# quadcopter.net
KiCad netlist of a schematic drawn in EAGLE
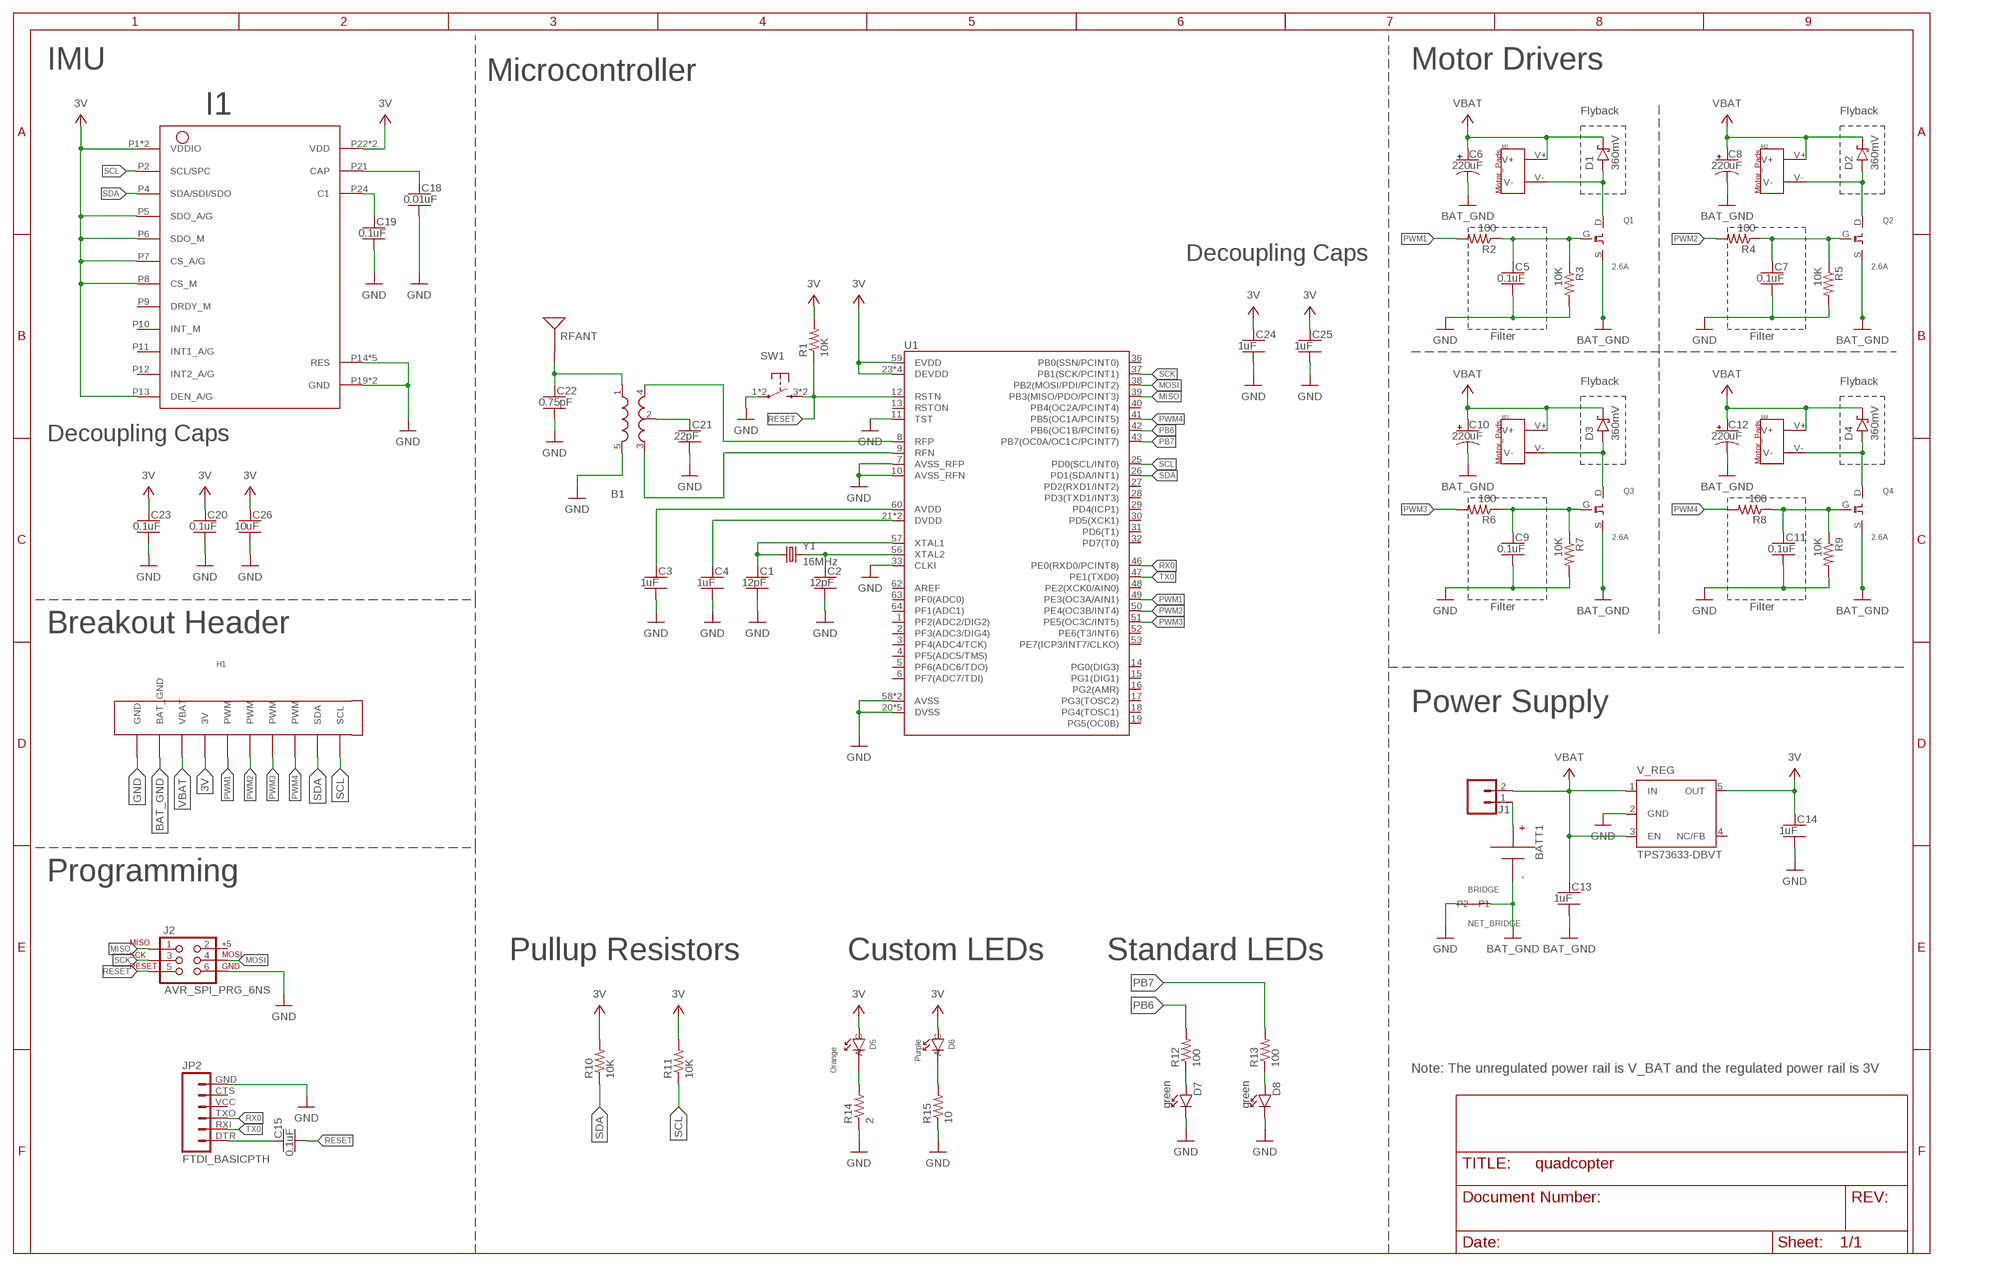
[diagram p0: schematic, sheet 1]

(export (version "E")
  (design (tool "Eeschema 10.0.6"))
  (components
    (comp (ref "B1")
      (value "BALUN0805")
      (footprint "eagle-import:BALUN")
      (fields
        (field (name "MFR") "Wurth Electronics Inc")
        (field (name "MPN") "748421245")
        (field (name "CREATOR") "Swanson")
        (field (name "REVIEWER") "Swanson")
      )
      (libsource (lib "eagle-import") (part "BALUN0805"))
    )
    (comp (ref "BATT1")
      (value "BATTERY-HUBSAN-W/HOLDER")
      (footprint "eagle-import:BATTERY-W_HOLDER-380MAH-HUBSAN")
      (fields
        (field (name "MFR") "HUBSAN")
        (field (name "MPN") "X4-H107C-8-in-1")
        (field (name "CREATOR") "Swanson")
        (field (name "REVIEWER") "Swanson")
      )
      (libsource (lib "eagle-import") (part "BATTERY-HUBSAN-W/HOLDER"))
    )
    (comp (ref "BRIDGE")
      (value "NET_BRIDGE")
      (footprint "eagle-import:NET_BRIDGE")
      (fields (field (name "CREATOR") "AGONZALES"))
      (libsource (lib "eagle-import") (part "NET_BRIDGE"))
    )
    (comp (ref "C1")
      (value "12pF")
      (footprint "eagle-import:CAPC2012X140_HS")
      (fields
        (field (name "MFR") "Murata Electronics North America")
        (field (name "MPN") "GRM21A5C2E120JW01D")
        (field (name "CREATOR") "Swanson")
        (field (name "REVIEWER") "Swanson")
      )
      (libsource (lib "eagle-import") (part "CAPACITOR-NP_SMD-2012-0805_CERAMIC-12PF"))
    )
    (comp (ref "C2")
      (value "12pF")
      (footprint "eagle-import:CAPC2012X140_HS")
      (fields
        (field (name "MFR") "Murata Electronics North America")
        (field (name "MPN") "GRM21A5C2E120JW01D")
        (field (name "CREATOR") "Swanson")
        (field (name "REVIEWER") "Swanson")
      )
      (libsource (lib "eagle-import") (part "CAPACITOR-NP_SMD-2012-0805_CERAMIC-12PF"))
    )
    (comp (ref "C3")
      (value "1uF")
      (footprint "eagle-import:CAPC2012X140_HS")
      (fields
        (field (name "MFR") "Taiyo Yuden")
        (field (name "MPN") "TMK212B7105KG-T")
        (field (name "CREATOR") "Swanson")
        (field (name "REVIEWER") "Swanson")
      )
      (libsource (lib "eagle-import") (part "CAPACITOR-NP_SMD-2012-0805_CERAMIC-1UF"))
    )
    (comp (ref "C4")
      (value "1uF")
      (footprint "eagle-import:CAPC2012X140_HS")
      (fields
        (field (name "MFR") "Taiyo Yuden")
        (field (name "MPN") "TMK212B7105KG-T")
        (field (name "CREATOR") "Swanson")
        (field (name "REVIEWER") "Swanson")
      )
      (libsource (lib "eagle-import") (part "CAPACITOR-NP_SMD-2012-0805_CERAMIC-1UF"))
    )
    (comp (ref "C5")
      (value "0.1uF")
      (footprint "eagle-import:CAPC2012X140_HS")
      (fields
        (field (name "MFR") "TDK")
        (field (name "MPN") "C2012X7R2A104K125AA")
        (field (name "CREATOR") "Swanson")
        (field (name "REVIEWER") "Swanson")
      )
      (libsource (lib "eagle-import") (part "CAPACITOR-NP_SMD-2012-0805_CERAMIC-0.1UF"))
    )
    (comp (ref "C6")
      (value "220uF")
      (footprint "eagle-import:CAPMP7343X310_HS")
      (fields
        (field (name "MFR") "AVX Corporation")
        (field (name "MPN") "TAJD227K006RNJ")
        (field (name "CREATOR") "Swanson")
        (field (name "REVIEWER") "Swanson")
      )
      (libsource (lib "eagle-import") (part "CAPACITOR-POL_SMD-7043-D_TANTALUM-220UF"))
    )
    (comp (ref "C7")
      (value "0.1uF")
      (footprint "eagle-import:CAPC2012X140_HS")
      (fields
        (field (name "MFR") "TDK")
        (field (name "MPN") "C2012X7R2A104K125AA")
        (field (name "CREATOR") "Swanson")
        (field (name "REVIEWER") "Swanson")
      )
      (libsource (lib "eagle-import") (part "CAPACITOR-NP_SMD-2012-0805_CERAMIC-0.1UF"))
    )
    (comp (ref "C8")
      (value "220uF")
      (footprint "eagle-import:CAPMP7343X310_HS")
      (fields
        (field (name "MFR") "AVX Corporation")
        (field (name "MPN") "TAJD227K006RNJ")
        (field (name "CREATOR") "Swanson")
        (field (name "REVIEWER") "Swanson")
      )
      (libsource (lib "eagle-import") (part "CAPACITOR-POL_SMD-7043-D_TANTALUM-220UF"))
    )
    (comp (ref "C9")
      (value "0.1uF")
      (footprint "eagle-import:CAPC2012X140_HS")
      (fields
        (field (name "MFR") "TDK")
        (field (name "MPN") "C2012X7R2A104K125AA")
        (field (name "CREATOR") "Swanson")
        (field (name "REVIEWER") "Swanson")
      )
      (libsource (lib "eagle-import") (part "CAPACITOR-NP_SMD-2012-0805_CERAMIC-0.1UF"))
    )
    (comp (ref "C10")
      (value "220uF")
      (footprint "eagle-import:CAPMP7343X310_HS")
      (fields
        (field (name "MFR") "AVX Corporation")
        (field (name "MPN") "TAJD227K006RNJ")
        (field (name "CREATOR") "Swanson")
        (field (name "REVIEWER") "Swanson")
      )
      (libsource (lib "eagle-import") (part "CAPACITOR-POL_SMD-7043-D_TANTALUM-220UF"))
    )
    (comp (ref "C11")
      (value "0.1uF")
      (footprint "eagle-import:CAPC2012X140_HS")
      (fields
        (field (name "MFR") "TDK")
        (field (name "MPN") "C2012X7R2A104K125AA")
        (field (name "CREATOR") "Swanson")
        (field (name "REVIEWER") "Swanson")
      )
      (libsource (lib "eagle-import") (part "CAPACITOR-NP_SMD-2012-0805_CERAMIC-0.1UF"))
    )
    (comp (ref "C12")
      (value "220uF")
      (footprint "eagle-import:CAPMP7343X310_HS")
      (fields
        (field (name "MFR") "AVX Corporation")
        (field (name "MPN") "TAJD227K006RNJ")
        (field (name "CREATOR") "Swanson")
        (field (name "REVIEWER") "Swanson")
      )
      (libsource (lib "eagle-import") (part "CAPACITOR-POL_SMD-7043-D_TANTALUM-220UF"))
    )
    (comp (ref "C13")
      (value "1uF")
      (footprint "eagle-import:CAPC2012X140_HS")
      (fields
        (field (name "MFR") "Taiyo Yuden")
        (field (name "MPN") "TMK212B7105KG-T")
        (field (name "CREATOR") "Swanson")
        (field (name "REVIEWER") "Swanson")
      )
      (libsource (lib "eagle-import") (part "CAPACITOR-NP_SMD-2012-0805_CERAMIC-1UF"))
    )
    (comp (ref "C14")
      (value "1uF")
      (footprint "eagle-import:CAPC2012X140_HS")
      (fields
        (field (name "MFR") "Taiyo Yuden")
        (field (name "MPN") "TMK212B7105KG-T")
        (field (name "CREATOR") "Swanson")
        (field (name "REVIEWER") "Swanson")
      )
      (libsource (lib "eagle-import") (part "CAPACITOR-NP_SMD-2012-0805_CERAMIC-1UF"))
    )
    (comp (ref "C15")
      (value "0.1uF")
      (footprint "eagle-import:CAPC2012X140_HS")
      (fields
        (field (name "MFR") "TDK")
        (field (name "MPN") "C2012X7R2A104K125AA")
        (field (name "CREATOR") "Swanson")
        (field (name "REVIEWER") "Swanson")
      )
      (libsource (lib "eagle-import") (part "CAPACITOR-NP_SMD-2012-0805_CERAMIC-0.1UF"))
    )
    (comp (ref "C18")
      (value "0.01uF")
      (footprint "eagle-import:CAPC2012X140_HS")
      (fields
        (field (name "MFR") "Knowles Syfer")
        (field (name "MPN") "0805J0500104KJT")
        (field (name "CREATOR") "Swanson")
        (field (name "REVIEWER") "Swanson")
      )
      (libsource (lib "eagle-import") (part "CAPACITOR-NP_SMD-2012-0805_CERAMIC-0.01UF"))
    )
    (comp (ref "C19")
      (value "0.1uF")
      (footprint "eagle-import:CAPC2012X140_HS")
      (fields
        (field (name "MFR") "TDK")
        (field (name "MPN") "C2012X7R2A104K125AA")
        (field (name "CREATOR") "Swanson")
        (field (name "REVIEWER") "Swanson")
      )
      (libsource (lib "eagle-import") (part "CAPACITOR-NP_SMD-2012-0805_CERAMIC-0.1UF"))
    )
    (comp (ref "C20")
      (value "0.1uF")
      (footprint "eagle-import:CAPC2012X140_HS")
      (fields
        (field (name "MFR") "TDK")
        (field (name "MPN") "C2012X7R2A104K125AA")
        (field (name "CREATOR") "Swanson")
        (field (name "REVIEWER") "Swanson")
      )
      (libsource (lib "eagle-import") (part "CAPACITOR-NP_SMD-2012-0805_CERAMIC-0.1UF"))
    )
    (comp (ref "C21")
      (value "22pF")
      (footprint "eagle-import:CAPC2012X140_HS")
      (fields
        (field (name "MFR") "Murata Electronics North America")
        (field (name "MPN") "GRM21A5C2E220JW01D")
        (field (name "CREATOR") "Swanson")
        (field (name "REVIEWER") "Swanson")
      )
      (libsource (lib "eagle-import") (part "CAPACITOR-NP_SMD-2012-0805_CERAMIC-22PF"))
    )
    (comp (ref "C22")
      (value "0.75pF")
      (footprint "eagle-import:CAPC2012X140_HS")
      (fields
        (field (name "MFR") "Murata Electronics North America")
        (field (name "MPN") "GQM2195C2AR75CB01D")
        (field (name "CREATOR") "Swanson")
        (field (name "REVIEWER") "Swanson")
      )
      (libsource (lib "eagle-import") (part "CAPACITOR-NP_SMD-2012-0805_CERAMIC-0.75PF"))
    )
    (comp (ref "C23")
      (value "0.1uF")
      (footprint "eagle-import:CAPC2012X140_HS")
      (fields
        (field (name "MFR") "TDK")
        (field (name "MPN") "C2012X7R2A104K125AA")
        (field (name "CREATOR") "Swanson")
        (field (name "REVIEWER") "Swanson")
      )
      (libsource (lib "eagle-import") (part "CAPACITOR-NP_SMD-2012-0805_CERAMIC-0.1UF"))
    )
    (comp (ref "C24")
      (value "1uF")
      (footprint "eagle-import:CAPC2012X140_HS")
      (fields
        (field (name "MFR") "Taiyo Yuden")
        (field (name "MPN") "TMK212B7105KG-T")
        (field (name "CREATOR") "Swanson")
        (field (name "REVIEWER") "Swanson")
      )
      (libsource (lib "eagle-import") (part "CAPACITOR-NP_SMD-2012-0805_CERAMIC-1UF"))
    )
    (comp (ref "C25")
      (value "1uF")
      (footprint "eagle-import:CAPC2012X140_HS")
      (fields
        (field (name "MFR") "Taiyo Yuden")
        (field (name "MPN") "TMK212B7105KG-T")
        (field (name "CREATOR") "Swanson")
        (field (name "REVIEWER") "Swanson")
      )
      (libsource (lib "eagle-import") (part "CAPACITOR-NP_SMD-2012-0805_CERAMIC-1UF"))
    )
    (comp (ref "C26")
      (value "10uF")
      (footprint "eagle-import:CAPC2012X140_HS")
      (fields
        (field (name "MFR") "TDK Corporation")
        (field (name "MPN") "C2012X5R1E106M085AC")
        (field (name "CREATOR") "Swanson")
        (field (name "REVIEWER") "Swanson")
      )
      (libsource (lib "eagle-import") (part "CAPACITOR-NP_SMD-2012-0805_CERAMIC-10UF"))
    )
    (comp (ref "D1")
      (value "360mV")
      (footprint "eagle-import:SOD3716X135_HS")
      (fields
        (field (name "MFR") "Toshiba Semiconductor and Storage")
        (field (name "MPN") "CRS08(TE85L,Q,M)")
        (field (name "CREATOR") "Swanson")
        (field (name "REVIEWER") "Swanson")
      )
      (libsource (lib "eagle-import") (part "DIODE-SCHOTTKY_SMD-SOD123-360MV"))
    )
    (comp (ref "D2")
      (value "360mV")
      (footprint "eagle-import:SOD3716X135_HS")
      (fields
        (field (name "MFR") "Toshiba Semiconductor and Storage")
        (field (name "MPN") "CRS08(TE85L,Q,M)")
        (field (name "CREATOR") "Swanson")
        (field (name "REVIEWER") "Swanson")
      )
      (libsource (lib "eagle-import") (part "DIODE-SCHOTTKY_SMD-SOD123-360MV"))
    )
    (comp (ref "D3")
      (value "360mV")
      (footprint "eagle-import:SOD3716X135_HS")
      (fields
        (field (name "MFR") "Toshiba Semiconductor and Storage")
        (field (name "MPN") "CRS08(TE85L,Q,M)")
        (field (name "CREATOR") "Swanson")
        (field (name "REVIEWER") "Swanson")
      )
      (libsource (lib "eagle-import") (part "DIODE-SCHOTTKY_SMD-SOD123-360MV"))
    )
    (comp (ref "D4")
      (value "360mV")
      (footprint "eagle-import:SOD3716X135_HS")
      (fields
        (field (name "MFR") "Toshiba Semiconductor and Storage")
        (field (name "MPN") "CRS08(TE85L,Q,M)")
        (field (name "CREATOR") "Swanson")
        (field (name "REVIEWER") "Swanson")
      )
      (libsource (lib "eagle-import") (part "DIODE-SCHOTTKY_SMD-SOD123-360MV"))
    )
    (comp (ref "D5")
      (value "Orange")
      (footprint "eagle-import:LED_ORANGE")
      (fields
        (field (name "MFR") "Lumileds")
        (field (name "MPN") "L135-O615003500001")
        (field (name "CREATOR") "Ben Phan")
      )
      (libsource (lib "eagle-import") (part "LED_ORANGE"))
    )
    (comp (ref "D6")
      (value "Purple")
      (footprint "eagle-import:LED_PURPLE")
      (fields
        (field (name "MFR") "Lumileds")
        (field (name "MPN") "L1SP-PRP2003500000")
        (field (name "CREATOR") "Ben Phan")
      )
      (libsource (lib "eagle-import") (part "LED_PURPLE"))
    )
    (comp (ref "D7")
      (value "green")
      (footprint "eagle-import:LEDSC125X200X120-2_HS")
      (fields
        (field (name "MFR") "Lite-On Inc")
        (field (name "MPN") "LTST-C170GKT")
        (field (name "CREATOR") "Swanson")
        (field (name "REVIEWER") "Swanson")
      )
      (libsource (lib "eagle-import") (part "DIODE-LED_SMD-2012-0805-GREEN"))
    )
    (comp (ref "D8")
      (value "green")
      (footprint "eagle-import:LEDSC125X200X120-2_HS")
      (fields
        (field (name "MFR") "Lite-On Inc")
        (field (name "MPN") "LTST-C170GKT")
        (field (name "CREATOR") "Swanson")
        (field (name "REVIEWER") "Swanson")
      )
      (libsource (lib "eagle-import") (part "DIODE-LED_SMD-2012-0805-GREEN"))
    )
    (comp (ref "H1")
      (value "BREAKOUT_HEADER")
      (footprint "eagle-import:BREAKOUT_HEADER")
      (fields (field (name "CREATOR") "Ben Phan"))
      (libsource (lib "eagle-import") (part "BREAKOUT_HEADER"))
    )
    (comp (ref "I1")
      (value "IMU_LSM9DS1TR")
      (footprint "eagle-import:IMU_LSM9DS1TR")
      (fields (field (name "MFR") "STMicroelectronics") (field (name "CREATOR") "AGONZALES"))
      (libsource (lib "eagle-import") (part "IMU_LSM9DS1TR"))
    )
    (comp (ref "J1")
      (value "MALE_HEADER_2POS-2X1-0.1IN")
      (footprint "eagle-import:MALE_HEADER_2X1_0.1IN")
      (fields
        (field (name "MFR") "3M")
        (field (name "MPN") "961102-6404-AR")
        (field (name "CREATOR") "SWANSON")
        (field (name "REVIEWER") "Swanson")
      )
      (libsource (lib "eagle-import") (part "MALE_HEADER_2POS-2X1-0.1IN"))
    )
    (comp (ref "J2")
      (value "AVR_SPI_PRG_6NS")
      (footprint "eagle-import:2X3-NS")
      (fields
        (field (name "MFR") "Amphenol FCI")
        (field (name "MPN") "67997-206HLF")
        (field (name "CREATOR") "Swanson")
        (field (name "REVIEWER") "Swanson")
      )
      (libsource (lib "eagle-import") (part "AVR_SPI_PRG_6NS"))
    )
    (comp (ref "JP2")
      (value "FTDI_BASICPTH")
      (footprint "eagle-import:FTDI_BASIC")
      (fields
        (field (name "MFR") "Amphenol FCI")
        (field (name "MPN") "68016-406HLF")
        (field (name "CREATOR") "Swanson")
        (field (name "REVIEWER") "Swanson")
      )
      (libsource (lib "eagle-import") (part "FTDI_BASICPTH"))
    )
    (comp (ref "M1")
      (value "MOTOR_PADS")
      (footprint "eagle-import:MOTOR_PADS")
      (fields
        (field (name "MFR") "NA")
        (field (name "CREATOR") "Swanson")
        (field (name "REVIEWER") "Swanson")
      )
      (libsource (lib "eagle-import") (part "MOTOR_PADS"))
    )
    (comp (ref "M2")
      (value "MOTOR_PADS")
      (footprint "eagle-import:MOTOR_PADS")
      (fields
        (field (name "MFR") "NA")
        (field (name "CREATOR") "Swanson")
        (field (name "REVIEWER") "Swanson")
      )
      (libsource (lib "eagle-import") (part "MOTOR_PADS"))
    )
    (comp (ref "M3")
      (value "MOTOR_PADS")
      (footprint "eagle-import:MOTOR_PADS")
      (fields
        (field (name "MFR") "NA")
        (field (name "CREATOR") "Swanson")
        (field (name "REVIEWER") "Swanson")
      )
      (libsource (lib "eagle-import") (part "MOTOR_PADS"))
    )
    (comp (ref "M4")
      (value "MOTOR_PADS")
      (footprint "eagle-import:MOTOR_PADS")
      (fields
        (field (name "MFR") "NA")
        (field (name "CREATOR") "Swanson")
        (field (name "REVIEWER") "Swanson")
      )
      (libsource (lib "eagle-import") (part "MOTOR_PADS"))
    )
    (comp (ref "Q1")
      (value "2.6A")
      (footprint "eagle-import:MOSFET_N-CHANNEL")
      (fields
        (field (name "MFR") "Vishay Siliconix")
        (field (name "MPN") "SI2302CDS-T1-E3")
        (field (name "CREATOR") "Ben Phan")
      )
      (libsource (lib "eagle-import") (part "N_CHANNEL_FET"))
    )
    (comp (ref "Q2")
      (value "2.6A")
      (footprint "eagle-import:MOSFET_N-CHANNEL")
      (fields
        (field (name "MFR") "Vishay Siliconix")
        (field (name "MPN") "SI2302CDS-T1-E3")
        (field (name "CREATOR") "Ben Phan")
      )
      (libsource (lib "eagle-import") (part "N_CHANNEL_FET"))
    )
    (comp (ref "Q3")
      (value "2.6A")
      (footprint "eagle-import:MOSFET_N-CHANNEL")
      (fields
        (field (name "MFR") "Vishay Siliconix")
        (field (name "MPN") "SI2302CDS-T1-E3")
        (field (name "CREATOR") "Ben Phan")
      )
      (libsource (lib "eagle-import") (part "N_CHANNEL_FET"))
    )
    (comp (ref "Q4")
      (value "2.6A")
      (footprint "eagle-import:MOSFET_N-CHANNEL")
      (fields
        (field (name "MFR") "Vishay Siliconix")
        (field (name "MPN") "SI2302CDS-T1-E3")
        (field (name "CREATOR") "Ben Phan")
      )
      (libsource (lib "eagle-import") (part "N_CHANNEL_FET"))
    )
    (comp (ref "R1")
      (value "10K")
      (footprint "eagle-import:RESC2012X60_HS")
      (fields
        (field (name "MFR") "Yageo")
        (field (name "MPN") "RC0805JR-0710KL")
        (field (name "CREATOR") "Swanson")
        (field (name "REVIEWER") "Swanson")
      )
      (libsource (lib "eagle-import") (part "RESISTOR_SMD-2012-0805-10K"))
    )
    (comp (ref "R2")
      (value "100")
      (footprint "eagle-import:RESC2012X60_HS")
      (fields
        (field (name "MFR") "Yageo")
        (field (name "MPN") "RC0805JR-07100RL")
        (field (name "CREATOR") "Swanson")
        (field (name "REVIEWER") "Swanson")
      )
      (libsource (lib "eagle-import") (part "RESISTOR_SMD-2012-0805-100"))
    )
    (comp (ref "R3")
      (value "10K")
      (footprint "eagle-import:RESC2012X60_HS")
      (fields
        (field (name "MFR") "Yageo")
        (field (name "MPN") "RC0805JR-0710KL")
        (field (name "CREATOR") "Swanson")
        (field (name "REVIEWER") "Swanson")
      )
      (libsource (lib "eagle-import") (part "RESISTOR_SMD-2012-0805-10K"))
    )
    (comp (ref "R4")
      (value "100")
      (footprint "eagle-import:RESC2012X60_HS")
      (fields
        (field (name "MFR") "Yageo")
        (field (name "MPN") "RC0805JR-07100RL")
        (field (name "CREATOR") "Swanson")
        (field (name "REVIEWER") "Swanson")
      )
      (libsource (lib "eagle-import") (part "RESISTOR_SMD-2012-0805-100"))
    )
    (comp (ref "R5")
      (value "10K")
      (footprint "eagle-import:RESC2012X60_HS")
      (fields
        (field (name "MFR") "Yageo")
        (field (name "MPN") "RC0805JR-0710KL")
        (field (name "CREATOR") "Swanson")
        (field (name "REVIEWER") "Swanson")
      )
      (libsource (lib "eagle-import") (part "RESISTOR_SMD-2012-0805-10K"))
    )
    (comp (ref "R6")
      (value "100")
      (footprint "eagle-import:RESC2012X60_HS")
      (fields
        (field (name "MFR") "Yageo")
        (field (name "MPN") "RC0805JR-07100RL")
        (field (name "CREATOR") "Swanson")
        (field (name "REVIEWER") "Swanson")
      )
      (libsource (lib "eagle-import") (part "RESISTOR_SMD-2012-0805-100"))
    )
    (comp (ref "R7")
      (value "10K")
      (footprint "eagle-import:RESC2012X60_HS")
      (fields
        (field (name "MFR") "Yageo")
        (field (name "MPN") "RC0805JR-0710KL")
        (field (name "CREATOR") "Swanson")
        (field (name "REVIEWER") "Swanson")
      )
      (libsource (lib "eagle-import") (part "RESISTOR_SMD-2012-0805-10K"))
    )
    (comp (ref "R8")
      (value "100")
      (footprint "eagle-import:RESC2012X60_HS")
      (fields
        (field (name "MFR") "Yageo")
        (field (name "MPN") "RC0805JR-07100RL")
        (field (name "CREATOR") "Swanson")
        (field (name "REVIEWER") "Swanson")
      )
      (libsource (lib "eagle-import") (part "RESISTOR_SMD-2012-0805-100"))
    )
    (comp (ref "R9")
      (value "10K")
      (footprint "eagle-import:RESC2012X60_HS")
      (fields
        (field (name "MFR") "Yageo")
        (field (name "MPN") "RC0805JR-0710KL")
        (field (name "CREATOR") "Swanson")
        (field (name "REVIEWER") "Swanson")
      )
      (libsource (lib "eagle-import") (part "RESISTOR_SMD-2012-0805-10K"))
    )
    (comp (ref "R10")
      (value "10K")
      (footprint "eagle-import:RESC2012X60_HS")
      (fields
        (field (name "MFR") "Yageo")
        (field (name "MPN") "RC0805JR-0710KL")
        (field (name "CREATOR") "Swanson")
        (field (name "REVIEWER") "Swanson")
      )
      (libsource (lib "eagle-import") (part "RESISTOR_SMD-2012-0805-10K"))
    )
    (comp (ref "R11")
      (value "10K")
      (footprint "eagle-import:RESC2012X60_HS")
      (fields
        (field (name "MFR") "Yageo")
        (field (name "MPN") "RC0805JR-0710KL")
        (field (name "CREATOR") "Swanson")
        (field (name "REVIEWER") "Swanson")
      )
      (libsource (lib "eagle-import") (part "RESISTOR_SMD-2012-0805-10K"))
    )
    (comp (ref "R12")
      (value "100")
      (footprint "eagle-import:RESC2012X60_HS")
      (fields
        (field (name "MFR") "Yageo")
        (field (name "MPN") "RC0805JR-07100RL")
        (field (name "CREATOR") "Swanson")
        (field (name "REVIEWER") "Swanson")
      )
      (libsource (lib "eagle-import") (part "RESISTOR_SMD-2012-0805-100"))
    )
    (comp (ref "R13")
      (value "100")
      (footprint "eagle-import:RESC2012X60_HS")
      (fields
        (field (name "MFR") "Yageo")
        (field (name "MPN") "RC0805JR-07100RL")
        (field (name "CREATOR") "Swanson")
        (field (name "REVIEWER") "Swanson")
      )
      (libsource (lib "eagle-import") (part "RESISTOR_SMD-2012-0805-100"))
    )
    (comp (ref "R14")
      (value "2")
      (footprint "eagle-import:RESISTOR_0805")
      (fields (field (name "CREATOR") "AGONZALES"))
      (libsource (lib "eagle-import") (part "0805_RES2_OHM"))
    )
    (comp (ref "R15")
      (value "10")
      (footprint "eagle-import:RESISTOR_0805")
      (fields (field (name "CREATOR") "AGONZALES"))
      (libsource (lib "eagle-import") (part "0805_RES10_OHM"))
    )
    (comp (ref "RFANT")
      (value "ANTENNA2SMD5")
      (footprint "eagle-import:ANTENNA-CHIP5")
      (fields
        (field (name "MFR") "Linx Technologies Inc.")
        (field (name "MPN") "ANT-2.45-CHP-T")
        (field (name "CREATOR") "Swanson")
        (field (name "REVIEWER") "Swanson")
      )
      (libsource (lib "eagle-import") (part "ANTENNA2SMD5"))
    )
    (comp (ref "SW1")
      (value "PUSHBUTTON_SMD-VERTICAL-1")
      (footprint "eagle-import:TE_FSM8JSMA_HS")
      (fields
        (field (name "MFR") "TE Connectivity Alcoswitch Switches")
        (field (name "MPN") "FSM4JSMA")
        (field (name "CREATOR") "Swanson")
        (field (name "REVIEWER") "Swanson")
      )
      (libsource (lib "eagle-import") (part "PUSHBUTTON_SMD-VERTICAL-1"))
    )
    (comp (ref "U1")
      (value "ATMEGA128RFA1")
      (footprint "eagle-import:QFN-64")
      (fields
        (field (name "MFR") "Atmel")
        (field (name "MPN") "ATMEGA128RFA1-ZUR00")
        (field (name "CREATOR") "Swanson")
        (field (name "REVIEWER") "Swanson")
      )
      (libsource (lib "eagle-import") (part "ATMEGA128RFA1"))
    )
    (comp (ref "V_REG")
      (value "TPS73633-DBVT")
      (footprint "eagle-import:SOT23-DBV")
      (fields
        (field (name "MFR") "Texas Instruments")
        (field (name "MPN") "LP3985IM5X-3.0/NOPB")
        (field (name "CREATOR") "Swanson")
        (field (name "REVIEWER") "Swanson")
      )
      (libsource (lib "eagle-import") (part "TPS73633-DBVT"))
    )
    (comp (ref "Y1")
      (value "16MHz")
      (footprint "eagle-import:CRYSTAL-SMD-5X3")
      (fields
        (field (name "MFR") "Abracon LLC")
        (field (name "MPN") "ABM3B-16.000MHZ-B2-T")
        (field (name "CREATOR") "Swanson")
        (field (name "REVIEWER") "Swanson")
      )
      (libsource (lib "eagle-import") (part "CRYSTAL5X3"))
    )
  )
  (nets
    (net (code "1") (name "3V") (class "Default")
      (node (ref "C14") (pin "1") (pinfunction "1_1") (pintype "passive"))
      (node (ref "C20") (pin "1") (pinfunction "1_1") (pintype "passive"))
      (node (ref "C23") (pin "1") (pinfunction "1_1") (pintype "passive"))
      (node (ref "C24") (pin "1") (pinfunction "1_1") (pintype "passive"))
      (node (ref "C25") (pin "1") (pinfunction "1_1") (pintype "passive"))
      (node (ref "C26") (pin "1") (pinfunction "1_1") (pintype "passive"))
      (node (ref "D5") (pin "A") (pinfunction "A_A") (pintype "bidirectional"))
      (node (ref "D6") (pin "A") (pinfunction "A_A") (pintype "bidirectional"))
      (node (ref "H1") (pin "1") (pinfunction "3V_1") (pintype "bidirectional"))
      (node (ref "I1") (pin "P1") (pinfunction "VDDIO_P1") (pintype "bidirectional"))
      (node (ref "I1") (pin "P13") (pinfunction "DEN_A/G_P13") (pintype "bidirectional"))
      (node (ref "I1") (pin "P22") (pinfunction "VDD_P22") (pintype "bidirectional"))
      (node (ref "I1") (pin "P23") (pinfunction "VDD_P23") (pintype "bidirectional"))
      (node (ref "I1") (pin "P3") (pinfunction "VDDIO_P3") (pintype "bidirectional"))
      (node (ref "I1") (pin "P5") (pinfunction "SDO_A/G_P5") (pintype "bidirectional"))
      (node (ref "I1") (pin "P6") (pinfunction "SDO_M_P6") (pintype "bidirectional"))
      (node (ref "I1") (pin "P7") (pinfunction "CS_A/G_P7") (pintype "bidirectional"))
      (node (ref "I1") (pin "P8") (pinfunction "CS_M_P8") (pintype "bidirectional"))
      (node (ref "R1") (pin "2") (pinfunction "2_2") (pintype "passive"))
      (node (ref "R10") (pin "2") (pinfunction "2_2") (pintype "passive"))
      (node (ref "R11") (pin "2") (pinfunction "2_2") (pintype "passive"))
      (node (ref "U1") (pin "23") (pinfunction "DEVDD_23") (pintype "bidirectional"))
      (node (ref "U1") (pin "34") (pinfunction "DEVDD_34") (pintype "bidirectional"))
      (node (ref "U1") (pin "44") (pinfunction "DEVDD_44") (pintype "bidirectional"))
      (node (ref "U1") (pin "54") (pinfunction "DEVDD_54") (pintype "bidirectional"))
      (node (ref "U1") (pin "59") (pinfunction "EVDD_59") (pintype "bidirectional"))
      (node (ref "V_REG") (pin "5") (pinfunction "OUT_5") (pintype "passive"))
    )
    (net (code "2") (name "BAT_GND") (class "Default")
      (node (ref "BATT1") (pin "-") (pinfunction "N_-") (pintype "bidirectional"))
      (node (ref "BRIDGE") (pin "P2") (pinfunction "P2_P2") (pintype "bidirectional"))
      (node (ref "C10") (pin "2") (pinfunction "-_2") (pintype "passive"))
      (node (ref "C12") (pin "2") (pinfunction "-_2") (pintype "passive"))
      (node (ref "C13") (pin "2") (pinfunction "2_2") (pintype "passive"))
      (node (ref "C6") (pin "2") (pinfunction "-_2") (pintype "passive"))
      (node (ref "C8") (pin "2") (pinfunction "-_2") (pintype "passive"))
      (node (ref "H1") (pin "2") (pinfunction "BAT_GND_2") (pintype "bidirectional"))
      (node (ref "Q1") (pin "S") (pinfunction "S_S") (pintype "bidirectional"))
      (node (ref "Q2") (pin "S") (pinfunction "S_S") (pintype "bidirectional"))
      (node (ref "Q3") (pin "S") (pinfunction "S_S") (pintype "bidirectional"))
      (node (ref "Q4") (pin "S") (pinfunction "S_S") (pintype "bidirectional"))
    )
    (net (code "3") (name "GND") (class "Default")
      (node (ref "B1") (pin "5") (pinfunction "GND_5") (pintype "bidirectional"))
      (node (ref "BRIDGE") (pin "P1") (pinfunction "P1_P1") (pintype "bidirectional"))
      (node (ref "C1") (pin "2") (pinfunction "2_2") (pintype "passive"))
      (node (ref "C11") (pin "2") (pinfunction "2_2") (pintype "passive"))
      (node (ref "C14") (pin "2") (pinfunction "2_2") (pintype "passive"))
      (node (ref "C18") (pin "2") (pinfunction "2_2") (pintype "passive"))
      (node (ref "C19") (pin "2") (pinfunction "2_2") (pintype "passive"))
      (node (ref "C2") (pin "2") (pinfunction "2_2") (pintype "passive"))
      (node (ref "C20") (pin "2") (pinfunction "2_2") (pintype "passive"))
      (node (ref "C21") (pin "2") (pinfunction "2_2") (pintype "passive"))
      (node (ref "C22") (pin "2") (pinfunction "2_2") (pintype "passive"))
      (node (ref "C23") (pin "2") (pinfunction "2_2") (pintype "passive"))
      (node (ref "C24") (pin "2") (pinfunction "2_2") (pintype "passive"))
      (node (ref "C25") (pin "2") (pinfunction "2_2") (pintype "passive"))
      (node (ref "C26") (pin "2") (pinfunction "2_2") (pintype "passive"))
      (node (ref "C3") (pin "2") (pinfunction "2_2") (pintype "passive"))
      (node (ref "C4") (pin "2") (pinfunction "2_2") (pintype "passive"))
      (node (ref "C5") (pin "2") (pinfunction "2_2") (pintype "passive"))
      (node (ref "C7") (pin "2") (pinfunction "2_2") (pintype "passive"))
      (node (ref "C9") (pin "2") (pinfunction "2_2") (pintype "passive"))
      (node (ref "D7") (pin "C") (pinfunction "C_C") (pintype "passive"))
      (node (ref "D8") (pin "C") (pinfunction "C_C") (pintype "passive"))
      (node (ref "H1") (pin "3") (pinfunction "GND_3") (pintype "bidirectional"))
      (node (ref "I1") (pin "P14") (pinfunction "RES_P14") (pintype "bidirectional"))
      (node (ref "I1") (pin "P15") (pinfunction "RES_P15") (pintype "bidirectional"))
      (node (ref "I1") (pin "P16") (pinfunction "RES_P16") (pintype "bidirectional"))
      (node (ref "I1") (pin "P17") (pinfunction "RES_P17") (pintype "bidirectional"))
      (node (ref "I1") (pin "P18") (pinfunction "RES_P18") (pintype "bidirectional"))
      (node (ref "I1") (pin "P19") (pinfunction "GND_P19") (pintype "bidirectional"))
      (node (ref "I1") (pin "P20") (pinfunction "GND_P20") (pintype "bidirectional"))
      (node (ref "J2") (pin "6") (pinfunction "6_6") (pintype "passive"))
      (node (ref "JP2") (pin "GND") (pinfunction "6_GND") (pintype "passive"))
      (node (ref "R14") (pin "IN") (pinfunction "1_IN") (pintype "passive"))
      (node (ref "R15") (pin "IN") (pinfunction "1_IN") (pintype "passive"))
      (node (ref "R3") (pin "2") (pinfunction "2_2") (pintype "passive"))
      (node (ref "R5") (pin "2") (pinfunction "2_2") (pintype "passive"))
      (node (ref "R7") (pin "2") (pinfunction "2_2") (pintype "passive"))
      (node (ref "R9") (pin "2") (pinfunction "2_2") (pintype "passive"))
      (node (ref "SW1") (pin "1") (pinfunction "1_1") (pintype "passive"))
      (node (ref "SW1") (pin "2") (pinfunction "1_2") (pintype "passive"))
      (node (ref "U1") (pin "10") (pinfunction "AVSS_RFN_10") (pintype "bidirectional"))
      (node (ref "U1") (pin "11") (pinfunction "TST_11") (pintype "bidirectional"))
      (node (ref "U1") (pin "20") (pinfunction "DVSS_20") (pintype "bidirectional"))
      (node (ref "U1") (pin "24") (pinfunction "DVSS_24") (pintype "bidirectional"))
      (node (ref "U1") (pin "33") (pinfunction "CLKI_33") (pintype "bidirectional"))
      (node (ref "U1") (pin "35") (pinfunction "DVSS_35") (pintype "bidirectional"))
      (node (ref "U1") (pin "45") (pinfunction "DVSS_45") (pintype "bidirectional"))
      (node (ref "U1") (pin "55") (pinfunction "DVSS_55") (pintype "bidirectional"))
      (node (ref "U1") (pin "58") (pinfunction "AVSS_58") (pintype "bidirectional"))
      (node (ref "U1") (pin "61") (pinfunction "AVSS_61") (pintype "bidirectional"))
      (node (ref "U1") (pin "7") (pinfunction "AVSS_RFP_7") (pintype "bidirectional"))
      (node (ref "V_REG") (pin "2") (pinfunction "GND_2") (pintype "input"))
    )
    (net (code "4") (name "MISO") (class "Default")
      (node (ref "J2") (pin "1") (pinfunction "1_1") (pintype "passive"))
      (node (ref "U1") (pin "39") (pinfunction "PB3(MISO/PDO/PCINT3)_39") (pintype "bidirectional"))
    )
    (net (code "5") (name "MOSI") (class "Default")
      (node (ref "J2") (pin "4") (pinfunction "4_4") (pintype "passive"))
      (node (ref "U1") (pin "38") (pinfunction "PB2(MOSI/PDI/PCINT2)_38") (pintype "bidirectional"))
    )
    (net (code "6") (name "Net-(B1-GND-Pad2)") (class "Default")
      (node (ref "B1") (pin "2") (pinfunction "GND_2") (pintype "bidirectional"))
      (node (ref "C21") (pin "1") (pinfunction "1_1") (pintype "passive"))
    )
    (net (code "7") (name "Net-(B1-IN)") (class "Default")
      (node (ref "B1") (pin "1") (pinfunction "IN_1") (pintype "bidirectional"))
      (node (ref "C22") (pin "1") (pinfunction "1_1") (pintype "passive"))
      (node (ref "RFANT") (pin "FEED") (pinfunction "SIGNAL_FEED") (pintype "bidirectional"))
    )
    (net (code "8") (name "Net-(B1-OUT1)") (class "Default")
      (node (ref "B1") (pin "4") (pinfunction "OUT1_4") (pintype "bidirectional"))
      (node (ref "U1") (pin "8") (pinfunction "RFP_8") (pintype "bidirectional"))
    )
    (net (code "9") (name "Net-(B1-OUT2)") (class "Default")
      (node (ref "B1") (pin "3") (pinfunction "OUT2_3") (pintype "bidirectional"))
      (node (ref "U1") (pin "9") (pinfunction "RFN_9") (pintype "bidirectional"))
    )
    (net (code "10") (name "Net-(BATT1-P)") (class "Default")
      (node (ref "BATT1") (pin "+") (pinfunction "P_+") (pintype "bidirectional"))
      (node (ref "J1") (pin "1") (pinfunction "1_1") (pintype "passive"))
    )
    (net (code "11") (name "Net-(C4-Pad1)") (class "Default")
      (node (ref "C4") (pin "1") (pinfunction "1_1") (pintype "passive"))
      (node (ref "U1") (pin "21") (pinfunction "DVDD_21") (pintype "bidirectional"))
      (node (ref "U1") (pin "22") (pinfunction "DVDD_22") (pintype "bidirectional"))
    )
    (net (code "12") (name "Net-(C5-Pad1)") (class "Default")
      (node (ref "C5") (pin "1") (pinfunction "1_1") (pintype "passive"))
      (node (ref "Q1") (pin "G") (pinfunction "G_G") (pintype "bidirectional"))
      (node (ref "R2") (pin "1") (pinfunction "1_1") (pintype "passive"))
      (node (ref "R3") (pin "1") (pinfunction "1_1") (pintype "passive"))
    )
    (net (code "13") (name "Net-(C7-Pad1)") (class "Default")
      (node (ref "C7") (pin "1") (pinfunction "1_1") (pintype "passive"))
      (node (ref "Q2") (pin "G") (pinfunction "G_G") (pintype "bidirectional"))
      (node (ref "R4") (pin "1") (pinfunction "1_1") (pintype "passive"))
      (node (ref "R5") (pin "1") (pinfunction "1_1") (pintype "passive"))
    )
    (net (code "14") (name "Net-(C9-Pad1)") (class "Default")
      (node (ref "C9") (pin "1") (pinfunction "1_1") (pintype "passive"))
      (node (ref "Q3") (pin "G") (pinfunction "G_G") (pintype "bidirectional"))
      (node (ref "R6") (pin "1") (pinfunction "1_1") (pintype "passive"))
      (node (ref "R7") (pin "1") (pinfunction "1_1") (pintype "passive"))
    )
    (net (code "15") (name "Net-(C11-Pad1)") (class "Default")
      (node (ref "C11") (pin "1") (pinfunction "1_1") (pintype "passive"))
      (node (ref "Q4") (pin "G") (pinfunction "G_G") (pintype "bidirectional"))
      (node (ref "R8") (pin "1") (pinfunction "1_1") (pintype "passive"))
      (node (ref "R9") (pin "1") (pinfunction "1_1") (pintype "passive"))
    )
    (net (code "16") (name "Net-(D1-PadA)") (class "Default")
      (node (ref "D1") (pin "A") (pinfunction "A_A") (pintype "passive"))
      (node (ref "M1") (pin "V-") (pinfunction "V-_V-") (pintype "bidirectional"))
      (node (ref "Q1") (pin "D") (pinfunction "D_D") (pintype "bidirectional"))
    )
    (net (code "17") (name "Net-(D2-PadA)") (class "Default")
      (node (ref "D2") (pin "A") (pinfunction "A_A") (pintype "passive"))
      (node (ref "M2") (pin "V-") (pinfunction "V-_V-") (pintype "bidirectional"))
      (node (ref "Q2") (pin "D") (pinfunction "D_D") (pintype "bidirectional"))
    )
    (net (code "18") (name "Net-(D3-PadA)") (class "Default")
      (node (ref "D3") (pin "A") (pinfunction "A_A") (pintype "passive"))
      (node (ref "M3") (pin "V-") (pinfunction "V-_V-") (pintype "bidirectional"))
      (node (ref "Q3") (pin "D") (pinfunction "D_D") (pintype "bidirectional"))
    )
    (net (code "19") (name "Net-(D4-PadA)") (class "Default")
      (node (ref "D4") (pin "A") (pinfunction "A_A") (pintype "passive"))
      (node (ref "M4") (pin "V-") (pinfunction "V-_V-") (pintype "bidirectional"))
      (node (ref "Q4") (pin "D") (pinfunction "D_D") (pintype "bidirectional"))
    )
    (net (code "20") (name "Net-(D7-PadA)") (class "Default")
      (node (ref "D7") (pin "A") (pinfunction "A_A") (pintype "passive"))
      (node (ref "R12") (pin "1") (pinfunction "1_1") (pintype "passive"))
    )
    (net (code "21") (name "Net-(D8-PadA)") (class "Default")
      (node (ref "D8") (pin "A") (pinfunction "A_A") (pintype "passive"))
      (node (ref "R13") (pin "1") (pinfunction "1_1") (pintype "passive"))
    )
    (net (code "22") (name "Net-(I1-C1)") (class "Default")
      (node (ref "C19") (pin "1") (pinfunction "1_1") (pintype "passive"))
      (node (ref "I1") (pin "P24") (pinfunction "C1_P24") (pintype "bidirectional"))
    )
    (net (code "23") (name "Net-(I1-CAP)") (class "Default")
      (node (ref "C18") (pin "1") (pinfunction "1_1") (pintype "passive"))
      (node (ref "I1") (pin "P21") (pinfunction "CAP_P21") (pintype "bidirectional"))
    )
    (net (code "24") (name "Net-(JP2-1)") (class "Default")
      (node (ref "C15") (pin "1") (pinfunction "1_1") (pintype "passive"))
      (node (ref "JP2") (pin "DTR") (pinfunction "1_DTR") (pintype "passive"))
    )
    (net (code "25") (name "Net-(R14-2)") (class "Default")
      (node (ref "D5") (pin "C") (pinfunction "C_C") (pintype "bidirectional"))
      (node (ref "R14") (pin "OUT") (pinfunction "2_OUT") (pintype "passive"))
    )
    (net (code "26") (name "Net-(R15-2)") (class "Default")
      (node (ref "D6") (pin "C") (pinfunction "C_C") (pintype "bidirectional"))
      (node (ref "R15") (pin "OUT") (pinfunction "2_OUT") (pintype "passive"))
    )
    (net (code "27") (name "Net-(U1-AVDD)") (class "Default")
      (node (ref "C3") (pin "1") (pinfunction "1_1") (pintype "passive"))
      (node (ref "U1") (pin "60") (pinfunction "AVDD_60") (pintype "bidirectional"))
    )
    (net (code "28") (name "Net-(U1-XTAL1)") (class "Default")
      (node (ref "C1") (pin "1") (pinfunction "1_1") (pintype "passive"))
      (node (ref "U1") (pin "57") (pinfunction "XTAL1_57") (pintype "bidirectional"))
      (node (ref "Y1") (pin "1") (pinfunction "1_1") (pintype "passive"))
    )
    (net (code "29") (name "Net-(U1-XTAL2)") (class "Default")
      (node (ref "C2") (pin "1") (pinfunction "1_1") (pintype "passive"))
      (node (ref "U1") (pin "56") (pinfunction "XTAL2_56") (pintype "bidirectional"))
      (node (ref "Y1") (pin "3") (pinfunction "2_3") (pintype "passive"))
    )
    (net (code "30") (name "PB6") (class "Default")
      (node (ref "R12") (pin "2") (pinfunction "2_2") (pintype "passive"))
      (node (ref "U1") (pin "42") (pinfunction "PB6(OC1B/PCINT6)_42") (pintype "bidirectional"))
    )
    (net (code "31") (name "PB7") (class "Default")
      (node (ref "R13") (pin "2") (pinfunction "2_2") (pintype "passive"))
      (node (ref "U1") (pin "43") (pinfunction "PB7(OC0A/OC1C/PCINT7)_43") (pintype "bidirectional"))
    )
    (net (code "32") (name "PWM1") (class "Default")
      (node (ref "H1") (pin "4") (pinfunction "PWM_4") (pintype "bidirectional"))
      (node (ref "R2") (pin "2") (pinfunction "2_2") (pintype "passive"))
      (node (ref "U1") (pin "49") (pinfunction "PE3(OC3A/AIN1)_49") (pintype "bidirectional"))
    )
    (net (code "33") (name "PWM2") (class "Default")
      (node (ref "H1") (pin "5") (pinfunction "PWM_5") (pintype "bidirectional"))
      (node (ref "R4") (pin "2") (pinfunction "2_2") (pintype "passive"))
      (node (ref "U1") (pin "50") (pinfunction "PE4(OC3B/INT4)_50") (pintype "bidirectional"))
    )
    (net (code "34") (name "PWM3") (class "Default")
      (node (ref "H1") (pin "6") (pinfunction "PWM_6") (pintype "bidirectional"))
      (node (ref "R6") (pin "2") (pinfunction "2_2") (pintype "passive"))
      (node (ref "U1") (pin "51") (pinfunction "PE5(OC3C/INT5)_51") (pintype "bidirectional"))
    )
    (net (code "35") (name "PWM4") (class "Default")
      (node (ref "H1") (pin "7") (pinfunction "PWM_7") (pintype "bidirectional"))
      (node (ref "R8") (pin "2") (pinfunction "2_2") (pintype "passive"))
      (node (ref "U1") (pin "41") (pinfunction "PB5(OC1A/PCINT5)_41") (pintype "bidirectional"))
    )
    (net (code "36") (name "RESET") (class "Default")
      (node (ref "C15") (pin "2") (pinfunction "2_2") (pintype "passive"))
      (node (ref "J2") (pin "5") (pinfunction "5_5") (pintype "passive"))
      (node (ref "R1") (pin "1") (pinfunction "1_1") (pintype "passive"))
      (node (ref "SW1") (pin "3") (pinfunction "2_3") (pintype "passive"))
      (node (ref "SW1") (pin "4") (pinfunction "2_4") (pintype "passive"))
      (node (ref "U1") (pin "12") (pinfunction "RSTN_12") (pintype "bidirectional"))
    )
    (net (code "37") (name "RX0") (class "Default")
      (node (ref "JP2") (pin "TXO") (pinfunction "3_TXO") (pintype "passive"))
      (node (ref "U1") (pin "46") (pinfunction "PE0(RXD0/PCINT8)_46") (pintype "bidirectional"))
    )
    (net (code "38") (name "SCK") (class "Default")
      (node (ref "J2") (pin "3") (pinfunction "3_3") (pintype "passive"))
      (node (ref "U1") (pin "37") (pinfunction "PB1(SCK/PCINT1)_37") (pintype "bidirectional"))
    )
    (net (code "39") (name "SCL") (class "Default")
      (node (ref "H1") (pin "8") (pinfunction "SCL_8") (pintype "bidirectional"))
      (node (ref "I1") (pin "P2") (pinfunction "SCL/SPC_P2") (pintype "bidirectional"))
      (node (ref "R11") (pin "1") (pinfunction "1_1") (pintype "passive"))
      (node (ref "U1") (pin "25") (pinfunction "PD0(SCL/INT0)_25") (pintype "bidirectional"))
    )
    (net (code "40") (name "SDA") (class "Default")
      (node (ref "H1") (pin "9") (pinfunction "SDA_9") (pintype "bidirectional"))
      (node (ref "I1") (pin "P4") (pinfunction "SDA/SDI/SDO_P4") (pintype "bidirectional"))
      (node (ref "R10") (pin "1") (pinfunction "1_1") (pintype "passive"))
      (node (ref "U1") (pin "26") (pinfunction "PD1(SDA/INT1)_26") (pintype "bidirectional"))
    )
    (net (code "41") (name "TX0") (class "Default")
      (node (ref "JP2") (pin "RXI") (pinfunction "2_RXI") (pintype "passive"))
      (node (ref "U1") (pin "47") (pinfunction "PE1(TXD0)_47") (pintype "bidirectional"))
    )
    (net (code "42") (name "VBAT") (class "Default")
      (node (ref "C10") (pin "1") (pinfunction "+_1") (pintype "passive"))
      (node (ref "C12") (pin "1") (pinfunction "+_1") (pintype "passive"))
      (node (ref "C13") (pin "1") (pinfunction "1_1") (pintype "passive"))
      (node (ref "C6") (pin "1") (pinfunction "+_1") (pintype "passive"))
      (node (ref "C8") (pin "1") (pinfunction "+_1") (pintype "passive"))
      (node (ref "D1") (pin "C") (pinfunction "C_C") (pintype "passive"))
      (node (ref "D2") (pin "C") (pinfunction "C_C") (pintype "passive"))
      (node (ref "D3") (pin "C") (pinfunction "C_C") (pintype "passive"))
      (node (ref "D4") (pin "C") (pinfunction "C_C") (pintype "passive"))
      (node (ref "H1") (pin "10") (pinfunction "VBAT_10") (pintype "bidirectional"))
      (node (ref "J1") (pin "2") (pinfunction "2_2") (pintype "passive"))
      (node (ref "M1") (pin "V+") (pinfunction "V+_V+") (pintype "bidirectional"))
      (node (ref "M2") (pin "V+") (pinfunction "V+_V+") (pintype "bidirectional"))
      (node (ref "M3") (pin "V+") (pinfunction "V+_V+") (pintype "bidirectional"))
      (node (ref "M4") (pin "V+") (pinfunction "V+_V+") (pintype "bidirectional"))
      (node (ref "V_REG") (pin "1") (pinfunction "IN_1") (pintype "input"))
      (node (ref "V_REG") (pin "3") (pinfunction "EN_3") (pintype "input"))
    )
    (net (code "43") (name "unconnected-(I1-DRDY_M-PadP9)") (class "Default")
      (node (ref "I1") (pin "P9") (pinfunction "DRDY_M_P9") (pintype "bidirectional"))
    )
    (net (code "44") (name "unconnected-(I1-INT1_A{slash}G-PadP11)") (class "Default")
      (node (ref "I1") (pin "P11") (pinfunction "INT1_A/G_P11") (pintype "bidirectional"))
    )
    (net (code "45") (name "unconnected-(I1-INT2_A{slash}G-PadP12)") (class "Default")
      (node (ref "I1") (pin "P12") (pinfunction "INT2_A/G_P12") (pintype "bidirectional"))
    )
    (net (code "46") (name "unconnected-(I1-INT_M-PadP10)") (class "Default")
      (node (ref "I1") (pin "P10") (pinfunction "INT_M_P10") (pintype "bidirectional"))
    )
    (net (code "47") (name "unconnected-(J2-Pad2)") (class "Default")
      (node (ref "J2") (pin "2") (pinfunction "2_2") (pintype "passive"))
    )
    (net (code "48") (name "unconnected-(JP2-4-PadVCC)") (class "Default")
      (node (ref "JP2") (pin "VCC") (pinfunction "4_VCC") (pintype "passive"))
    )
    (net (code "49") (name "unconnected-(JP2-5-PadCTS)") (class "Default")
      (node (ref "JP2") (pin "CTS") (pinfunction "5_CTS") (pintype "passive"))
    )
    (net (code "50") (name "unconnected-(U1-AREF-Pad62)") (class "Default")
      (node (ref "U1") (pin "62") (pinfunction "AREF_62") (pintype "bidirectional"))
    )
    (net (code "51") (name "unconnected-(U1-PB0(SSN{slash}PCINT0)-Pad36)") (class "Default")
      (node (ref "U1") (pin "36") (pinfunction "PB0(SSN/PCINT0)_36") (pintype "bidirectional"))
    )
    (net (code "52") (name "unconnected-(U1-PB4(OC2A{slash}PCINT4)-Pad40)") (class "Default")
      (node (ref "U1") (pin "40") (pinfunction "PB4(OC2A/PCINT4)_40") (pintype "bidirectional"))
    )
    (net (code "53") (name "unconnected-(U1-PD2(RXD1{slash}INT2)-Pad27)") (class "Default")
      (node (ref "U1") (pin "27") (pinfunction "PD2(RXD1/INT2)_27") (pintype "bidirectional"))
    )
    (net (code "54") (name "unconnected-(U1-PD3(TXD1{slash}INT3)-Pad28)") (class "Default")
      (node (ref "U1") (pin "28") (pinfunction "PD3(TXD1/INT3)_28") (pintype "bidirectional"))
    )
    (net (code "55") (name "unconnected-(U1-PD4(ICP1)-Pad29)") (class "Default")
      (node (ref "U1") (pin "29") (pinfunction "PD4(ICP1)_29") (pintype "bidirectional"))
    )
    (net (code "56") (name "unconnected-(U1-PD5(XCK1)-Pad30)") (class "Default")
      (node (ref "U1") (pin "30") (pinfunction "PD5(XCK1)_30") (pintype "bidirectional"))
    )
    (net (code "57") (name "unconnected-(U1-PD6(T1)-Pad31)") (class "Default")
      (node (ref "U1") (pin "31") (pinfunction "PD6(T1)_31") (pintype "bidirectional"))
    )
    (net (code "58") (name "unconnected-(U1-PD7(T0)-Pad32)") (class "Default")
      (node (ref "U1") (pin "32") (pinfunction "PD7(T0)_32") (pintype "bidirectional"))
    )
    (net (code "59") (name "unconnected-(U1-PE2(XCK0{slash}AIN0)-Pad48)") (class "Default")
      (node (ref "U1") (pin "48") (pinfunction "PE2(XCK0/AIN0)_48") (pintype "bidirectional"))
    )
    (net (code "60") (name "unconnected-(U1-PE6(T3{slash}INT6)-Pad52)") (class "Default")
      (node (ref "U1") (pin "52") (pinfunction "PE6(T3/INT6)_52") (pintype "bidirectional"))
    )
    (net (code "61") (name "unconnected-(U1-PE7(ICP3{slash}INT7{slash}CLKO)-Pad53)") (class "Default")
      (node (ref "U1") (pin "53") (pinfunction "PE7(ICP3/INT7/CLKO)_53") (pintype "bidirectional"))
    )
    (net (code "62") (name "unconnected-(U1-PF0(ADC0)-Pad63)") (class "Default")
      (node (ref "U1") (pin "63") (pinfunction "PF0(ADC0)_63") (pintype "bidirectional"))
    )
    (net (code "63") (name "unconnected-(U1-PF1(ADC1)-Pad64)") (class "Default")
      (node (ref "U1") (pin "64") (pinfunction "PF1(ADC1)_64") (pintype "bidirectional"))
    )
    (net (code "64") (name "unconnected-(U1-PF2(ADC2{slash}DIG2)-Pad1)") (class "Default")
      (node (ref "U1") (pin "1") (pinfunction "PF2(ADC2/DIG2)_1") (pintype "bidirectional"))
    )
    (net (code "65") (name "unconnected-(U1-PF3(ADC3{slash}DIG4)-Pad2)") (class "Default")
      (node (ref "U1") (pin "2") (pinfunction "PF3(ADC3/DIG4)_2") (pintype "bidirectional"))
    )
    (net (code "66") (name "unconnected-(U1-PF4(ADC4{slash}TCK)-Pad3)") (class "Default")
      (node (ref "U1") (pin "3") (pinfunction "PF4(ADC4/TCK)_3") (pintype "bidirectional"))
    )
    (net (code "67") (name "unconnected-(U1-PF5(ADC5{slash}TMS)-Pad4)") (class "Default")
      (node (ref "U1") (pin "4") (pinfunction "PF5(ADC5/TMS)_4") (pintype "bidirectional"))
    )
    (net (code "68") (name "unconnected-(U1-PF6(ADC6{slash}TDO)-Pad5)") (class "Default")
      (node (ref "U1") (pin "5") (pinfunction "PF6(ADC6/TDO)_5") (pintype "bidirectional"))
    )
    (net (code "69") (name "unconnected-(U1-PF7(ADC7{slash}TDI)-Pad6)") (class "Default")
      (node (ref "U1") (pin "6") (pinfunction "PF7(ADC7/TDI)_6") (pintype "bidirectional"))
    )
    (net (code "70") (name "unconnected-(U1-PG0(DIG3)-Pad14)") (class "Default")
      (node (ref "U1") (pin "14") (pinfunction "PG0(DIG3)_14") (pintype "bidirectional"))
    )
    (net (code "71") (name "unconnected-(U1-PG1(DIG1)-Pad15)") (class "Default")
      (node (ref "U1") (pin "15") (pinfunction "PG1(DIG1)_15") (pintype "bidirectional"))
    )
    (net (code "72") (name "unconnected-(U1-PG2(AMR)-Pad16)") (class "Default")
      (node (ref "U1") (pin "16") (pinfunction "PG2(AMR)_16") (pintype "bidirectional"))
    )
    (net (code "73") (name "unconnected-(U1-PG3(TOSC2)-Pad17)") (class "Default")
      (node (ref "U1") (pin "17") (pinfunction "PG3(TOSC2)_17") (pintype "bidirectional"))
    )
    (net (code "74") (name "unconnected-(U1-PG4(TOSC1)-Pad18)") (class "Default")
      (node (ref "U1") (pin "18") (pinfunction "PG4(TOSC1)_18") (pintype "bidirectional"))
    )
    (net (code "75") (name "unconnected-(U1-PG5(OC0B)-Pad19)") (class "Default")
      (node (ref "U1") (pin "19") (pinfunction "PG5(OC0B)_19") (pintype "bidirectional"))
    )
    (net (code "76") (name "unconnected-(U1-RSTON-Pad13)") (class "Default")
      (node (ref "U1") (pin "13") (pinfunction "RSTON_13") (pintype "bidirectional"))
    )
    (net (code "77") (name "unconnected-(V_REG-NC{slash}FB-Pad4)") (class "Default")
      (node (ref "V_REG") (pin "4") (pinfunction "NC/FB_4") (pintype "passive"))
    )
  )
)
